# 2024210097__2.net
KiCad netlist of a schematic drawn in EasyEDA Pro
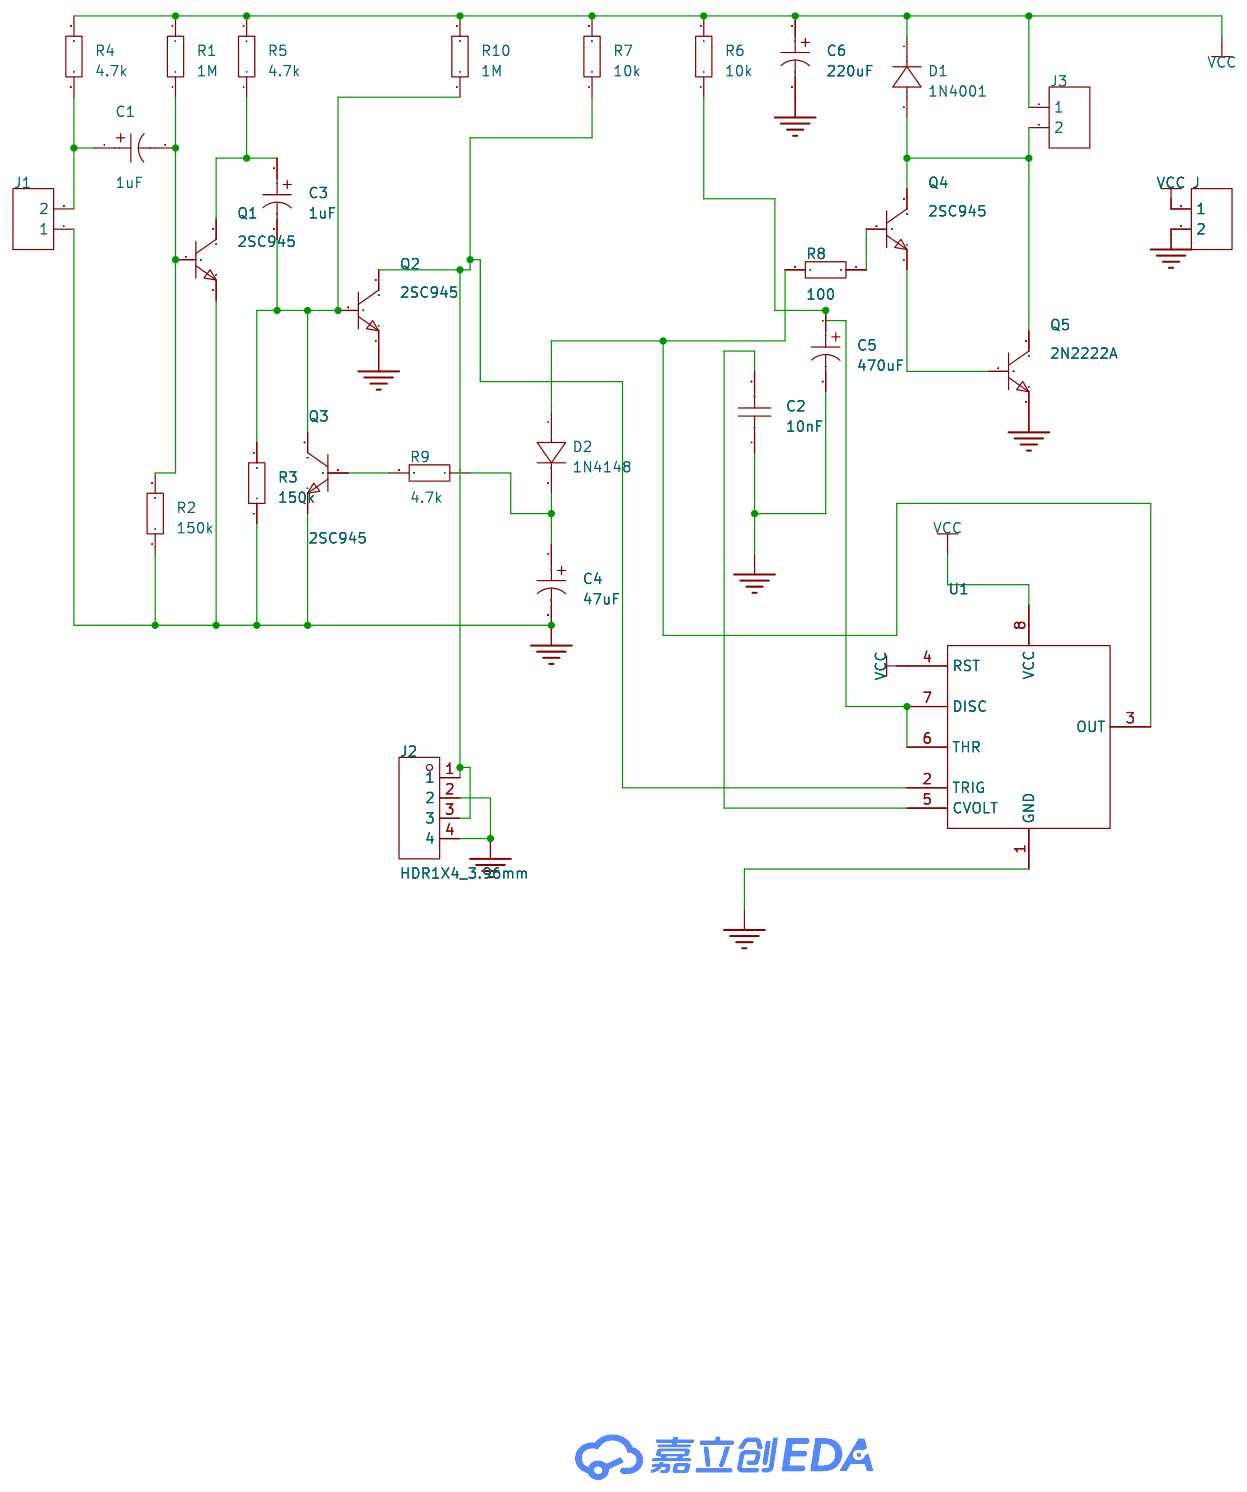
[diagram p0: schematic sheet]

(export (version "E")
  (design (tool "Eeschema 10.0.6"))
  (components
    (comp (ref "C1")
      (value "1uF")
      (footprint "easyedapro:CAP-TH_BD6.3-P2.50-D0.5-FD")
      (description "容值:1uF;精度:±20%;额定电压:-;纹波电流:-;等效串联电阻:-;")
      (fields (field (name "Manufacturer Part") "UVR2E010MED") (field (name "Manufacturer") "Nichicon(尼吉康)"))
      (libsource (lib "easyedapro") (part "UVR2E010MED"))
    )
    (comp (ref "C2")
      (value "10nF")
      (footprint "easyedapro:C1206")
      (libsource (lib "easyedapro") (part "10NF"))
    )
    (comp (ref "C3")
      (value "1uF")
      (footprint "easyedapro:CAP-TH_BD6.3-P2.50-D0.5-FD")
      (description "容值:1uF;精度:±20%;额定电压:-;纹波电流:-;等效串联电阻:-;")
      (fields (field (name "Manufacturer Part") "UVR2E010MED") (field (name "Manufacturer") "Nichicon(尼吉康)"))
      (libsource (lib "easyedapro") (part "UVR2E010MED"))
    )
    (comp (ref "C4")
      (value "47uF")
      (footprint "easyedapro:CAP-TH_BD6.3-P2.50-D0.5-FD")
      (description "容值:47uF;精度:±20%;额定电压:63V;纹波电流:-;等效串联电阻(ESR):-;")
      (fields (field (name "Manufacturer Part") "CD26G1JM470E120T") (field (name "Manufacturer") "创慧电子"))
      (libsource (lib "easyedapro") (part "CD26G1JM470E120T"))
    )
    (comp (ref "C5")
      (value "470uF")
      (footprint "easyedapro:CAP-TH_BD8.0-P5.00-D0.6-FD")
      (description "容值:470uF;精度:±20%;额定电压:25V;纹波电流:-;等效串联电阻:-;")
      (fields
        (field (name "Manufacturer Part") "ERR1EM471F12P50")
        (field (name "Manufacturer") "AISHI(艾华集团)")
      )
      (libsource (lib "easyedapro") (part "ERR1EM471F12P50"))
    )
    (comp (ref "C6")
      (value "220uF")
      (footprint "easyedapro:CAP-TH_BD8.0-P3.50-D0.6-FD")
      (description "容值:220uF;精度:±20%;额定电压:25V;纹波电流:360mA@10kHz;等效串联电阻(ESR):-;")
      (fields
        (field (name "Manufacturer Part") "UKA1E221MPD1TD")
        (field (name "Manufacturer") "Nichicon(尼吉康)")
      )
      (libsource (lib "easyedapro") (part "UKA1E221MPD1TD"))
    )
    (comp (ref "D1")
      (value "1N4001")
      (footprint "easyedapro:SMA_L4.3-W2.6-LS5.1-RD")
      (libsource (lib "easyedapro") (part "1N4001_C9900008134"))
    )
    (comp (ref "D2")
      (value "1N4148")
      (footprint "easyedapro:DO-35_BD2.2-L4.0-D0.50_1N4148")
      (fields (field (name "Manufacturer") "LJ(朗捷)"))
      (libsource (lib "easyedapro") (part "1N4148_C18195411"))
    )
    (comp (ref "J")
      (value "~")
      (footprint "easyedapro:HDR-TH_2P-P2.54-V-F")
      (description "插孔结构:1x2P;间距:2.54mm;行距:-;安装类型:直插;排数:单排;总孔位数:2P;塑高:-;触头材质:-;触头镀层:-;")
      (fields (field (name "Manufacturer Part") "2.54-1*2P母") (field (name "Manufacturer") "BOOMELE(博穆精密)"))
      (libsource (lib "easyedapro") (part "Header-Female-2.54_1x2"))
    )
    (comp (ref "J1")
      (value "~")
      (footprint "easyedapro:HDR-TH_2P-P2.54-V-F")
      (description "插孔结构:1x2P;间距:2.54mm;行距:-;安装类型:直插;排数:单排;总孔位数:2P;塑高:-;触头材质:-;触头镀层:-;")
      (fields (field (name "Manufacturer Part") "2.54-1*2P母") (field (name "Manufacturer") "BOOMELE(博穆精密)"))
      (libsource (lib "easyedapro") (part "Header-Female-2.54_1x2"))
    )
    (comp (ref "J2")
      (value "HDR1X4_3.96mm")
      (footprint "easyedapro:CONN-TH_4P-P3.96_FWF39601-S04S22W1B")
      (libsource (lib "easyedapro") (part "HDR1X4_3.96MM"))
    )
    (comp (ref "J3")
      (value "~")
      (footprint "easyedapro:HDR-TH_2P-P2.54-V-F")
      (description "插孔结构:1x2P;间距:2.54mm;行距:-;安装类型:直插;排数:单排;总孔位数:2P;塑高:-;触头材质:-;触头镀层:-;")
      (fields (field (name "Manufacturer Part") "2.54-1*2P母") (field (name "Manufacturer") "BOOMELE(博穆精密)"))
      (libsource (lib "easyedapro") (part "Header-Female-2.54_1x2"))
    )
    (comp (ref "Q1")
      (value "2SC945")
      (footprint "easyedapro:TO-92-3_L4.9-W3.7-P1.27-L")
      (fields (field (name "Manufacturer") "ST(先科)"))
      (libsource (lib "easyedapro") (part "2SC945_C2987754"))
    )
    (comp (ref "Q2")
      (value "2SC945")
      (footprint "easyedapro:TO-92-3_L4.9-W3.7-P1.27-L")
      (fields (field (name "Manufacturer") "ST(先科)"))
      (libsource (lib "easyedapro") (part "2SC945_C2987754"))
    )
    (comp (ref "Q3")
      (value "2SC945")
      (footprint "easyedapro:TO-92-3_L4.9-W3.7-P1.27-L")
      (fields (field (name "Manufacturer") "ST(先科)"))
      (libsource (lib "easyedapro") (part "2SC945_C2987754"))
    )
    (comp (ref "Q4")
      (value "2SC945")
      (footprint "easyedapro:TO-92-3_L4.9-W3.7-P1.27-L")
      (fields (field (name "Manufacturer") "ST(先科)"))
      (libsource (lib "easyedapro") (part "2SC945_C2987754"))
    )
    (comp (ref "Q5")
      (value "2N2222A")
      (footprint "easyedapro:TO-92-3_L4.9-W3.7-P1.27-L")
      (description "晶体管类型:NPN;集电极电流(Ic):600mA;集射极击穿电压(Vceo):40V;功率(Pd):625mW;直流电流增益(hFE@Ic,Vce):40@500mA,10V;")
      (fields (field (name "Manufacturer") "ST(先科)"))
      (libsource (lib "easyedapro") (part "2N2222"))
    )
    (comp (ref "R1") (value "1M") (footprint "easyedapro:R0603") (libsource (lib "easyedapro") (part "电阻")))
    (comp (ref "R2") (value "150k") (footprint "easyedapro:R0603") (libsource (lib "easyedapro") (part "电阻")))
    (comp (ref "R3") (value "150k") (footprint "easyedapro:R0603") (libsource (lib "easyedapro") (part "电阻")))
    (comp (ref "R4") (value "4.7k") (footprint "easyedapro:R0603") (libsource (lib "easyedapro") (part "电阻")))
    (comp (ref "R5") (value "4.7k") (footprint "easyedapro:R0603") (libsource (lib "easyedapro") (part "电阻")))
    (comp (ref "R6") (value "10k") (footprint "easyedapro:R0603") (libsource (lib "easyedapro") (part "电阻")))
    (comp (ref "R7") (value "10k") (footprint "easyedapro:R0603") (libsource (lib "easyedapro") (part "电阻")))
    (comp (ref "R8") (value "100") (footprint "easyedapro:R0603") (libsource (lib "easyedapro") (part "电阻")))
    (comp (ref "R9") (value "4.7k") (footprint "easyedapro:R0603") (libsource (lib "easyedapro") (part "电阻")))
    (comp (ref "R10") (value "1M") (footprint "easyedapro:R0603") (libsource (lib "easyedapro") (part "电阻")))
    (comp (ref "U1") (value "~") (libsource (lib "easyedapro") (part "555")))
  )
  (nets
    (net (code "1") (name "GND") (class "Default")
      (node (ref "C2") (pin "1") (pinfunction "1_1") (pintype "unspecified"))
      (node (ref "C4") (pin "2") (pinfunction "2_2") (pintype "input"))
      (node (ref "C5") (pin "2") (pinfunction "2_2") (pintype "input"))
      (node (ref "C6") (pin "2") (pinfunction "2_2") (pintype "input"))
      (node (ref "J") (pin "2") (pinfunction "2_2") (pintype "input"))
      (node (ref "J1") (pin "1") (pinfunction "1_1") (pintype "input"))
      (node (ref "J2") (pin "2") (pinfunction "2_2") (pintype "unspecified"))
      (node (ref "J2") (pin "4") (pinfunction "4_4") (pintype "unspecified"))
      (node (ref "Q1") (pin "1") (pinfunction "E_1") (pintype "unspecified"))
      (node (ref "Q2") (pin "1") (pinfunction "E_1") (pintype "unspecified"))
      (node (ref "Q3") (pin "1") (pinfunction "E_1") (pintype "unspecified"))
      (node (ref "Q5") (pin "1") (pinfunction "E_1") (pintype "unspecified"))
      (node (ref "R2") (pin "1") (pinfunction "1_1") (pintype "input"))
      (node (ref "R3") (pin "1") (pinfunction "1_1") (pintype "input"))
      (node (ref "U1") (pin "1") (pinfunction "GND_1") (pintype "input"))
    )
    (net (code "2") (name "Net-(C1-Pad1)") (class "Default")
      (node (ref "C1") (pin "1") (pinfunction "1_1") (pintype "input"))
      (node (ref "J1") (pin "2") (pinfunction "2_2") (pintype "input"))
      (node (ref "R4") (pin "1") (pinfunction "1_1") (pintype "input"))
    )
    (net (code "3") (name "Net-(D1-A)") (class "Default")
      (node (ref "D1") (pin "2") (pinfunction "A_2") (pintype "unspecified"))
      (node (ref "J3") (pin "2") (pinfunction "2_2") (pintype "input"))
      (node (ref "Q4") (pin "2") (pinfunction "C_2") (pintype "unspecified"))
      (node (ref "Q5") (pin "3") (pinfunction "C_3") (pintype "unspecified"))
    )
    (net (code "4") (name "Net-(D2-A)") (class "Default")
      (node (ref "D2") (pin "1") (pinfunction "A_1") (pintype "unspecified"))
      (node (ref "R8") (pin "2") (pinfunction "2_2") (pintype "input"))
      (node (ref "U1") (pin "3") (pinfunction "OUT_3") (pintype "input"))
    )
    (net (code "5") (name "Net-(D2-C)") (class "Default")
      (node (ref "C4") (pin "1") (pinfunction "1_1") (pintype "input"))
      (node (ref "D2") (pin "2") (pinfunction "C_2") (pintype "unspecified"))
      (node (ref "R9") (pin "1") (pinfunction "1_1") (pintype "input"))
    )
    (net (code "6") (name "Net-(Q1-B)") (class "Default")
      (node (ref "C1") (pin "2") (pinfunction "2_2") (pintype "input"))
      (node (ref "Q1") (pin "3") (pinfunction "B_3") (pintype "unspecified"))
      (node (ref "R1") (pin "1") (pinfunction "1_1") (pintype "input"))
      (node (ref "R2") (pin "2") (pinfunction "2_2") (pintype "input"))
    )
    (net (code "7") (name "Net-(Q1-C)") (class "Default")
      (node (ref "C3") (pin "1") (pinfunction "1_1") (pintype "input"))
      (node (ref "Q1") (pin "2") (pinfunction "C_2") (pintype "unspecified"))
      (node (ref "R5") (pin "1") (pinfunction "1_1") (pintype "input"))
    )
    (net (code "8") (name "Net-(Q2-B)") (class "Default")
      (node (ref "C3") (pin "2") (pinfunction "2_2") (pintype "input"))
      (node (ref "Q2") (pin "3") (pinfunction "B_3") (pintype "unspecified"))
      (node (ref "Q3") (pin "2") (pinfunction "C_2") (pintype "unspecified"))
      (node (ref "R10") (pin "1") (pinfunction "1_1") (pintype "input"))
      (node (ref "R3") (pin "2") (pinfunction "2_2") (pintype "input"))
    )
    (net (code "9") (name "Net-(Q2-C)") (class "Default")
      (node (ref "J2") (pin "1") (pinfunction "1_1") (pintype "unspecified"))
      (node (ref "J2") (pin "3") (pinfunction "3_3") (pintype "unspecified"))
      (node (ref "Q2") (pin "2") (pinfunction "C_2") (pintype "unspecified"))
      (node (ref "R7") (pin "1") (pinfunction "1_1") (pintype "input"))
      (node (ref "U1") (pin "2") (pinfunction "TRIG_2") (pintype "input"))
    )
    (net (code "10") (name "Net-(Q3-B)") (class "Default")
      (node (ref "Q3") (pin "3") (pinfunction "B_3") (pintype "unspecified"))
      (node (ref "R9") (pin "2") (pinfunction "2_2") (pintype "input"))
    )
    (net (code "11") (name "Net-(Q4-B)") (class "Default")
      (node (ref "Q4") (pin "3") (pinfunction "B_3") (pintype "unspecified"))
      (node (ref "R8") (pin "1") (pinfunction "1_1") (pintype "input"))
    )
    (net (code "12") (name "Net-(Q4-E)") (class "Default")
      (node (ref "Q4") (pin "1") (pinfunction "E_1") (pintype "unspecified"))
      (node (ref "Q5") (pin "2") (pinfunction "B_2") (pintype "unspecified"))
    )
    (net (code "13") (name "Net-(U1-CVOLT)") (class "Default")
      (node (ref "C2") (pin "2") (pinfunction "2_2") (pintype "unspecified"))
      (node (ref "U1") (pin "5") (pinfunction "CVOLT_5") (pintype "input"))
    )
    (net (code "14") (name "Net-(U1-DISC)") (class "Default")
      (node (ref "C5") (pin "1") (pinfunction "1_1") (pintype "input"))
      (node (ref "R6") (pin "1") (pinfunction "1_1") (pintype "input"))
      (node (ref "U1") (pin "6") (pinfunction "THR_6") (pintype "input"))
      (node (ref "U1") (pin "7") (pinfunction "DISC_7") (pintype "input"))
    )
    (net (code "15") (name "VCC") (class "Default")
      (node (ref "C6") (pin "1") (pinfunction "1_1") (pintype "input"))
      (node (ref "D1") (pin "1") (pinfunction "K_1") (pintype "unspecified"))
      (node (ref "J") (pin "1") (pinfunction "1_1") (pintype "input"))
      (node (ref "J3") (pin "1") (pinfunction "1_1") (pintype "input"))
      (node (ref "R1") (pin "2") (pinfunction "2_2") (pintype "input"))
      (node (ref "R10") (pin "2") (pinfunction "2_2") (pintype "input"))
      (node (ref "R4") (pin "2") (pinfunction "2_2") (pintype "input"))
      (node (ref "R5") (pin "2") (pinfunction "2_2") (pintype "input"))
      (node (ref "R6") (pin "2") (pinfunction "2_2") (pintype "input"))
      (node (ref "R7") (pin "2") (pinfunction "2_2") (pintype "input"))
      (node (ref "U1") (pin "4") (pinfunction "RST_4") (pintype "input"))
      (node (ref "U1") (pin "8") (pinfunction "VCC_8") (pintype "input"))
    )
  )
)
